# motor-drive.net
KiCad netlist of a schematic drawn in Altium Designer
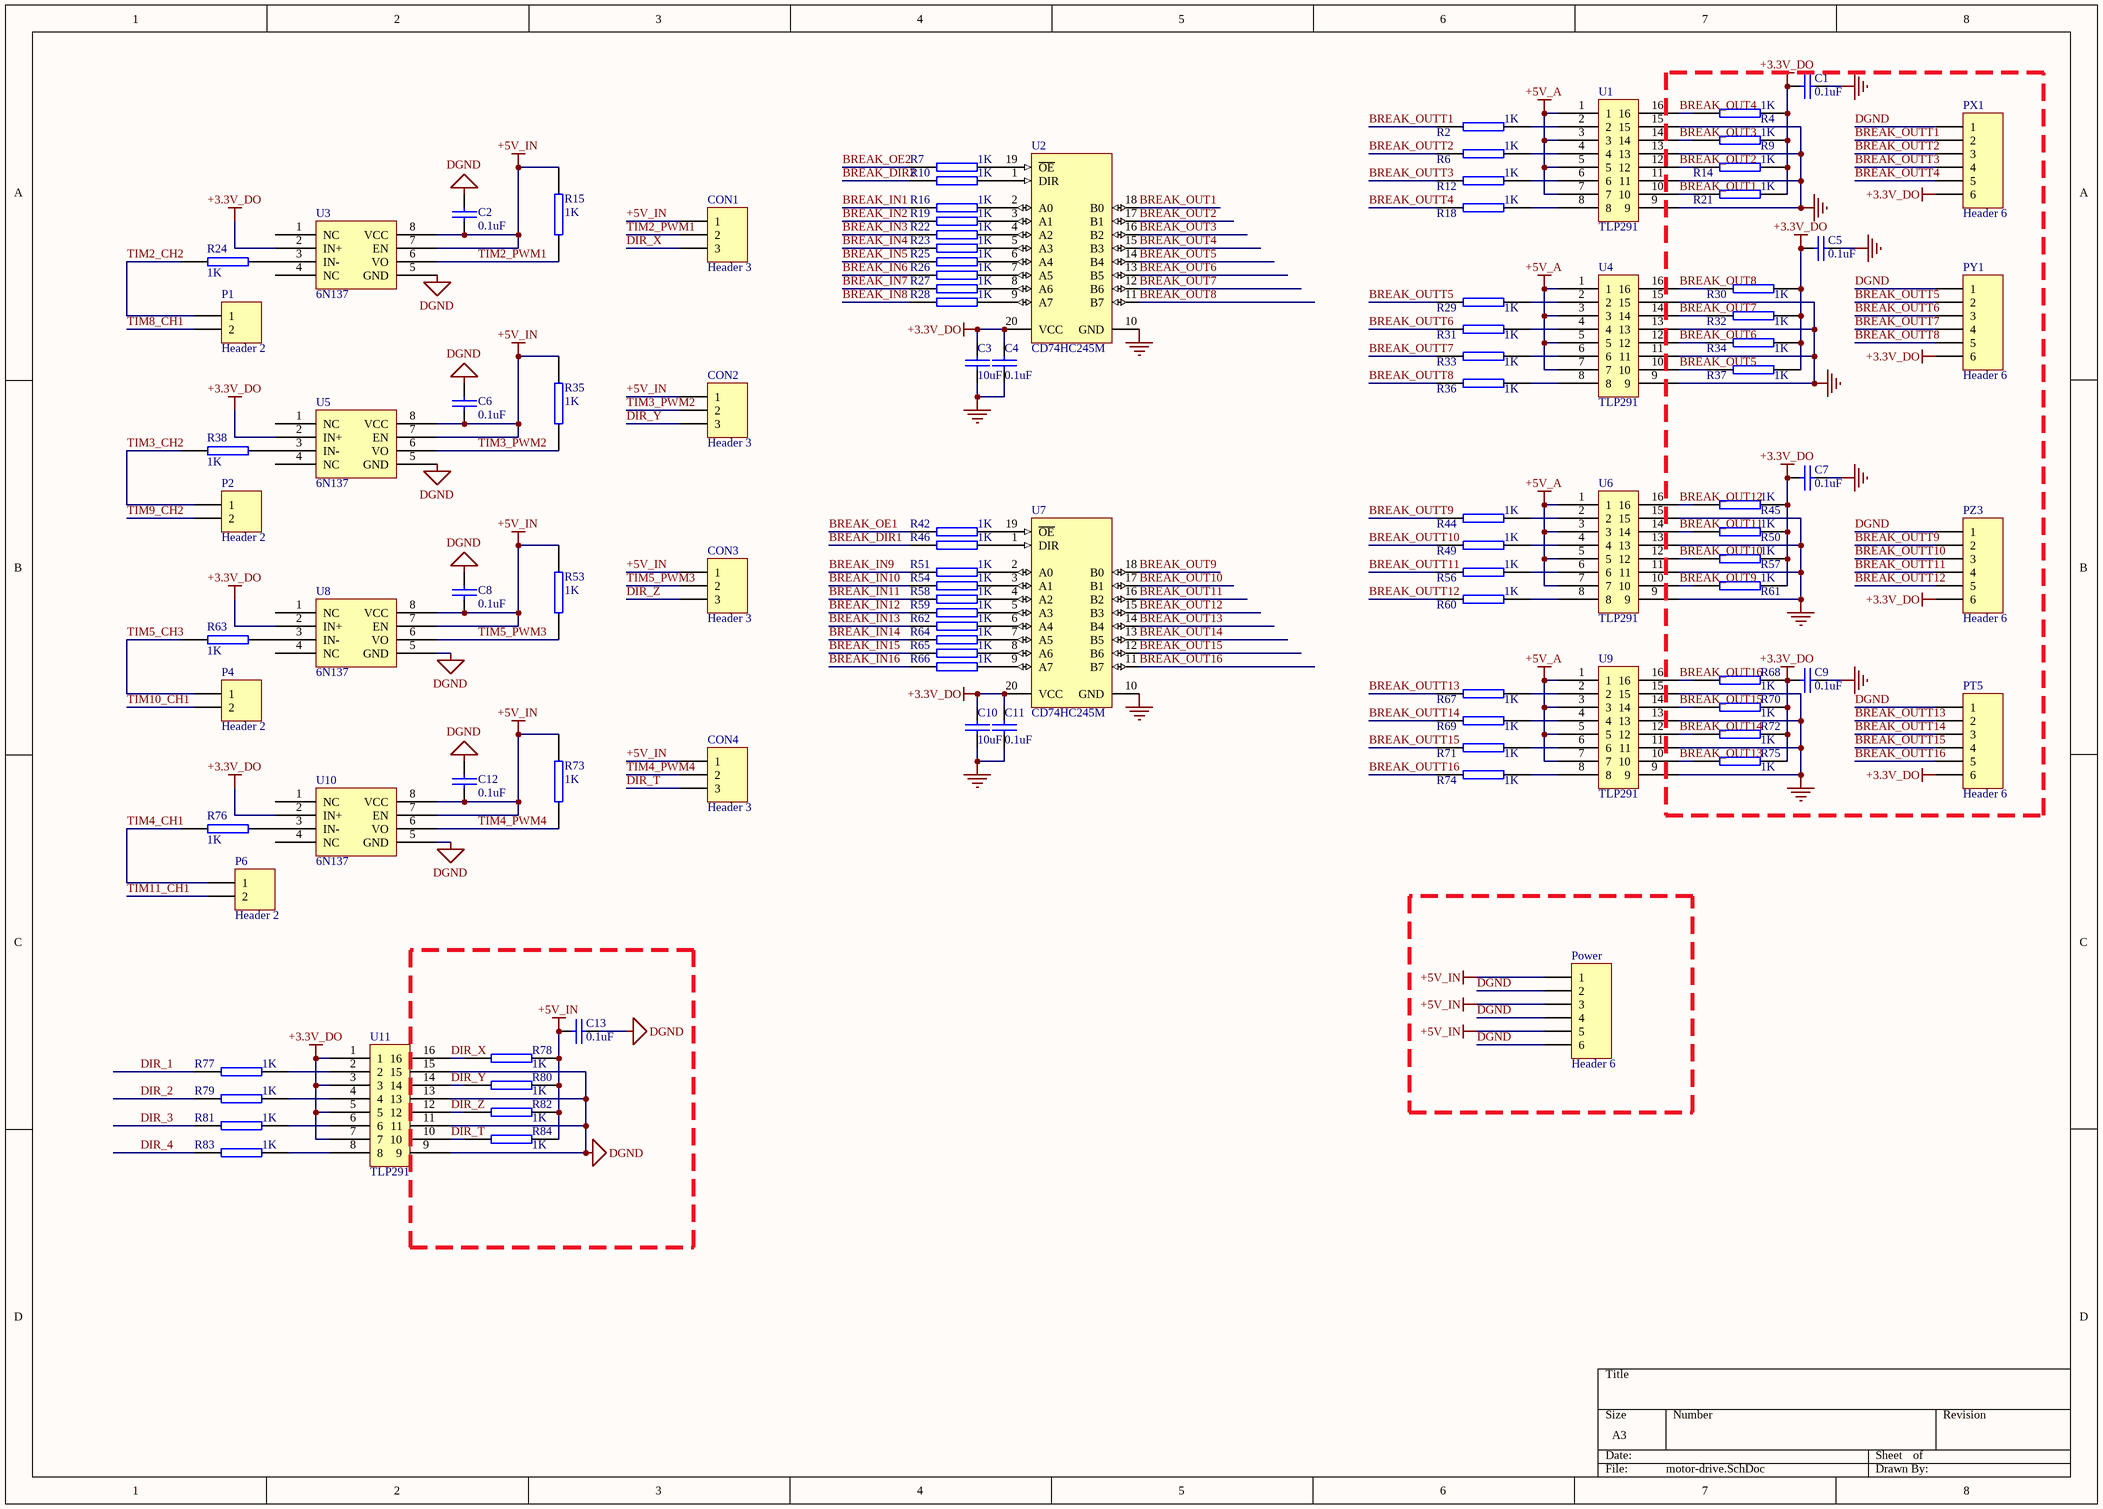
[diagram p0: motor-drive.SchDoc]

(export (version "E")
  (design (tool "Eeschema 10.0.6"))
  (components
    (comp (ref "C1")
      (value "0.1uF")
      (footprint "0805")
      (description "Capacitor")
      (libsource (lib "*") (part "CAP"))
    )
    (comp (ref "C2")
      (value "0.1uF")
      (footprint "0805")
      (description "Capacitor")
      (libsource (lib "*") (part "CAP"))
    )
    (comp (ref "C3")
      (value "10uF")
      (footprint "0805")
      (description "Capacitor")
      (libsource (lib "*") (part "CAP"))
    )
    (comp (ref "C4")
      (value "0.1uF")
      (footprint "0805")
      (description "Capacitor")
      (libsource (lib "*") (part "CAP"))
    )
    (comp (ref "C5")
      (value "0.1uF")
      (footprint "0805")
      (description "Capacitor")
      (libsource (lib "*") (part "CAP"))
    )
    (comp (ref "C6")
      (value "0.1uF")
      (footprint "0805")
      (description "Capacitor")
      (libsource (lib "*") (part "CAP"))
    )
    (comp (ref "C7")
      (value "0.1uF")
      (footprint "0805")
      (description "Capacitor")
      (libsource (lib "*") (part "CAP"))
    )
    (comp (ref "C8")
      (value "0.1uF")
      (footprint "0805")
      (description "Capacitor")
      (libsource (lib "*") (part "CAP"))
    )
    (comp (ref "C9")
      (value "0.1uF")
      (footprint "0805")
      (description "Capacitor")
      (libsource (lib "*") (part "CAP"))
    )
    (comp (ref "C10")
      (value "10uF")
      (footprint "0805")
      (description "Capacitor")
      (libsource (lib "*") (part "CAP"))
    )
    (comp (ref "C11")
      (value "0.1uF")
      (footprint "0805")
      (description "Capacitor")
      (libsource (lib "*") (part "CAP"))
    )
    (comp (ref "C12")
      (value "0.1uF")
      (footprint "0805")
      (description "Capacitor")
      (libsource (lib "*") (part "CAP"))
    )
    (comp (ref "C13")
      (value "0.1uF")
      (footprint "0805")
      (description "Capacitor")
      (libsource (lib "*") (part "CAP"))
    )
    (comp (ref "CON1")
      (value "Header 3")
      (footprint "CON3")
      (description "Header, 3-Pin")
      (fields (field (name "PUBLISHER") "Altium Limited"))
      (libsource (lib "Miscellaneous Connectors") (part "Header 3"))
    )
    (comp (ref "CON2")
      (value "Header 3")
      (footprint "CON3")
      (description "Header, 3-Pin")
      (fields (field (name "PUBLISHER") "Altium Limited"))
      (libsource (lib "Miscellaneous Connectors") (part "Header 3"))
    )
    (comp (ref "CON3")
      (value "Header 3")
      (footprint "CON3")
      (description "Header, 3-Pin")
      (fields (field (name "PUBLISHER") "Altium Limited"))
      (libsource (lib "Miscellaneous Connectors") (part "Header 3"))
    )
    (comp (ref "CON4")
      (value "Header 3")
      (footprint "CON3")
      (description "Header, 3-Pin")
      (fields (field (name "PUBLISHER") "Altium Limited"))
      (libsource (lib "Miscellaneous Connectors") (part "Header 3"))
    )
    (comp (ref "P1")
      (value "Header 2")
      (footprint "HDR1X2")
      (description "Header, 2-Pin")
      (fields (field (name "PUBLISHER") "Altium Limited"))
      (libsource (lib "Miscellaneous Connectors") (part "Header 2"))
    )
    (comp (ref "P2")
      (value "Header 2")
      (footprint "HDR1X2")
      (description "Header, 2-Pin")
      (fields (field (name "PUBLISHER") "Altium Limited"))
      (libsource (lib "Miscellaneous Connectors") (part "Header 2"))
    )
    (comp (ref "P4")
      (value "Header 2")
      (footprint "HDR1X2")
      (description "Header, 2-Pin")
      (fields (field (name "PUBLISHER") "Altium Limited"))
      (libsource (lib "Miscellaneous Connectors") (part "Header 2"))
    )
    (comp (ref "P6")
      (value "Header 2")
      (footprint "HDR1X2")
      (description "Header, 2-Pin")
      (fields (field (name "PUBLISHER") "Altium Limited"))
      (libsource (lib "Miscellaneous Connectors") (part "Header 2"))
    )
    (comp (ref "Power")
      (value "Header 6")
      (footprint "HDR1X6")
      (description "Header, 6-Pin")
      (fields (field (name "PUBLISHER") "Altium Limited"))
      (libsource (lib "Miscellaneous Connectors") (part "Header 6"))
    )
    (comp (ref "PT5")
      (value "Header 6")
      (footprint "HDR1X6")
      (description "Header, 6-Pin")
      (fields (field (name "PUBLISHER") "Altium Limited"))
      (libsource (lib "Miscellaneous Connectors") (part "Header 6"))
    )
    (comp (ref "PX1")
      (value "Header 6")
      (footprint "HDR1X6")
      (description "Header, 6-Pin")
      (fields (field (name "PUBLISHER") "Altium Limited"))
      (libsource (lib "Miscellaneous Connectors") (part "Header 6"))
    )
    (comp (ref "PY1")
      (value "Header 6")
      (footprint "HDR1X6")
      (description "Header, 6-Pin")
      (fields (field (name "PUBLISHER") "Altium Limited"))
      (libsource (lib "Miscellaneous Connectors") (part "Header 6"))
    )
    (comp (ref "PZ3")
      (value "Header 6")
      (footprint "HDR1X6")
      (description "Header, 6-Pin")
      (fields (field (name "PUBLISHER") "Altium Limited"))
      (libsource (lib "Miscellaneous Connectors") (part "Header 6"))
    )
    (comp (ref "R2") (value "1K") (footprint "0805") (libsource (lib "*") (part "RES2")))
    (comp (ref "R4") (value "1K") (footprint "0805") (libsource (lib "*") (part "RES2")))
    (comp (ref "R6") (value "1K") (footprint "0805") (libsource (lib "*") (part "RES2")))
    (comp (ref "R7") (value "1K") (footprint "0805") (libsource (lib "*") (part "RES2")))
    (comp (ref "R9") (value "1K") (footprint "0805") (libsource (lib "*") (part "RES2")))
    (comp (ref "R10") (value "1K") (footprint "0805") (libsource (lib "*") (part "RES2")))
    (comp (ref "R12") (value "1K") (footprint "0805") (libsource (lib "*") (part "RES2")))
    (comp (ref "R14") (value "1K") (footprint "0805") (libsource (lib "*") (part "RES2")))
    (comp (ref "R15") (value "1K") (footprint "0805") (libsource (lib "*") (part "RES2")))
    (comp (ref "R16") (value "1K") (footprint "0805") (libsource (lib "*") (part "RES2")))
    (comp (ref "R18") (value "1K") (footprint "0805") (libsource (lib "*") (part "RES2")))
    (comp (ref "R19") (value "1K") (footprint "0805") (libsource (lib "*") (part "RES2")))
    (comp (ref "R21") (value "1K") (footprint "0805") (libsource (lib "*") (part "RES2")))
    (comp (ref "R22") (value "1K") (footprint "0805") (libsource (lib "*") (part "RES2")))
    (comp (ref "R23") (value "1K") (footprint "0805") (libsource (lib "*") (part "RES2")))
    (comp (ref "R24") (value "1K") (footprint "0805") (libsource (lib "*") (part "RES2")))
    (comp (ref "R25") (value "1K") (footprint "0805") (libsource (lib "*") (part "RES2")))
    (comp (ref "R26") (value "1K") (footprint "0805") (libsource (lib "*") (part "RES2")))
    (comp (ref "R27") (value "1K") (footprint "0805") (libsource (lib "*") (part "RES2")))
    (comp (ref "R28") (value "1K") (footprint "0805") (libsource (lib "*") (part "RES2")))
    (comp (ref "R29") (value "1K") (footprint "0805") (libsource (lib "*") (part "RES2")))
    (comp (ref "R30") (value "1K") (footprint "0805") (libsource (lib "*") (part "RES2")))
    (comp (ref "R31") (value "1K") (footprint "0805") (libsource (lib "*") (part "RES2")))
    (comp (ref "R32") (value "1K") (footprint "0805") (libsource (lib "*") (part "RES2")))
    (comp (ref "R33") (value "1K") (footprint "0805") (libsource (lib "*") (part "RES2")))
    (comp (ref "R34") (value "1K") (footprint "0805") (libsource (lib "*") (part "RES2")))
    (comp (ref "R35") (value "1K") (footprint "0805") (libsource (lib "*") (part "RES2")))
    (comp (ref "R36") (value "1K") (footprint "0805") (libsource (lib "*") (part "RES2")))
    (comp (ref "R37") (value "1K") (footprint "0805") (libsource (lib "*") (part "RES2")))
    (comp (ref "R38") (value "1K") (footprint "0805") (libsource (lib "*") (part "RES2")))
    (comp (ref "R42") (value "1K") (footprint "0805") (libsource (lib "*") (part "RES2")))
    (comp (ref "R44") (value "1K") (footprint "0805") (libsource (lib "*") (part "RES2")))
    (comp (ref "R45") (value "1K") (footprint "0805") (libsource (lib "*") (part "RES2")))
    (comp (ref "R46") (value "1K") (footprint "0805") (libsource (lib "*") (part "RES2")))
    (comp (ref "R49") (value "1K") (footprint "0805") (libsource (lib "*") (part "RES2")))
    (comp (ref "R50") (value "1K") (footprint "0805") (libsource (lib "*") (part "RES2")))
    (comp (ref "R51") (value "1K") (footprint "0805") (libsource (lib "*") (part "RES2")))
    (comp (ref "R53") (value "1K") (footprint "0805") (libsource (lib "*") (part "RES2")))
    (comp (ref "R54") (value "1K") (footprint "0805") (libsource (lib "*") (part "RES2")))
    (comp (ref "R56") (value "1K") (footprint "0805") (libsource (lib "*") (part "RES2")))
    (comp (ref "R57") (value "1K") (footprint "0805") (libsource (lib "*") (part "RES2")))
    (comp (ref "R58") (value "1K") (footprint "0805") (libsource (lib "*") (part "RES2")))
    (comp (ref "R59") (value "1K") (footprint "0805") (libsource (lib "*") (part "RES2")))
    (comp (ref "R60") (value "1K") (footprint "0805") (libsource (lib "*") (part "RES2")))
    (comp (ref "R61") (value "1K") (footprint "0805") (libsource (lib "*") (part "RES2")))
    (comp (ref "R62") (value "1K") (footprint "0805") (libsource (lib "*") (part "RES2")))
    (comp (ref "R63") (value "1K") (footprint "0805") (libsource (lib "*") (part "RES2")))
    (comp (ref "R64") (value "1K") (footprint "0805") (libsource (lib "*") (part "RES2")))
    (comp (ref "R65") (value "1K") (footprint "0805") (libsource (lib "*") (part "RES2")))
    (comp (ref "R66") (value "1K") (footprint "0805") (libsource (lib "*") (part "RES2")))
    (comp (ref "R67") (value "1K") (footprint "0805") (libsource (lib "*") (part "RES2")))
    (comp (ref "R68") (value "1K") (footprint "0805") (libsource (lib "*") (part "RES2")))
    (comp (ref "R69") (value "1K") (footprint "0805") (libsource (lib "*") (part "RES2")))
    (comp (ref "R70") (value "1K") (footprint "0805") (libsource (lib "*") (part "RES2")))
    (comp (ref "R71") (value "1K") (footprint "0805") (libsource (lib "*") (part "RES2")))
    (comp (ref "R72") (value "1K") (footprint "0805") (libsource (lib "*") (part "RES2")))
    (comp (ref "R73") (value "1K") (footprint "0805") (libsource (lib "*") (part "RES2")))
    (comp (ref "R74") (value "1K") (footprint "0805") (libsource (lib "*") (part "RES2")))
    (comp (ref "R75") (value "1K") (footprint "0805") (libsource (lib "*") (part "RES2")))
    (comp (ref "R76") (value "1K") (footprint "0805") (libsource (lib "*") (part "RES2")))
    (comp (ref "R77") (value "1K") (footprint "0805") (libsource (lib "*") (part "RES2")))
    (comp (ref "R78") (value "1K") (footprint "0805") (libsource (lib "*") (part "RES2")))
    (comp (ref "R79") (value "1K") (footprint "0805") (libsource (lib "*") (part "RES2")))
    (comp (ref "R80") (value "1K") (footprint "0805") (libsource (lib "*") (part "RES2")))
    (comp (ref "R81") (value "1K") (footprint "0805") (libsource (lib "*") (part "RES2")))
    (comp (ref "R82") (value "1K") (footprint "0805") (libsource (lib "*") (part "RES2")))
    (comp (ref "R83") (value "1K") (footprint "0805") (libsource (lib "*") (part "RES2")))
    (comp (ref "R84") (value "1K") (footprint "0805") (libsource (lib "*") (part "RES2")))
    (comp (ref "U1")
      (value "TLP291")
      (footprint "SOIC-TLP291-4-16N")
      (description "光耦隔离")
      (libsource (lib "tlp291-4") (part "TLP291-4"))
    )
    (comp (ref "U2")
      (value "CD74HC245M")
      (footprint "DW0020A_N")
      (description "High Speed CMOS Logic Non-Inverting Octal-Bus Transceivers with 3-State Outputs, DW0020A, TUBE")
      (fields
        (field (name "GENERIC PART NUMBER") "CD74HC245")
        (field (name "MANUFACTURER") "Texas Instruments")
      )
      (libsource (lib "TI_Logic_Buffer,Driver,Transceiver") (part "CD74HC245M"))
    )
    (comp (ref "U3") (value "6N137") (footprint "SO-8") (libsource (lib "*") (part "HCPL2400")))
    (comp (ref "U4")
      (value "TLP291")
      (footprint "SOIC-TLP291-4-16N")
      (description "光耦隔离")
      (libsource (lib "tlp291-4") (part "TLP291-4"))
    )
    (comp (ref "U5") (value "6N137") (footprint "SO-8") (libsource (lib "*") (part "HCPL2400")))
    (comp (ref "U6")
      (value "TLP291")
      (footprint "SOIC-TLP291-4-16N")
      (description "光耦隔离")
      (libsource (lib "tlp291-4") (part "TLP291-4"))
    )
    (comp (ref "U7")
      (value "CD74HC245M")
      (footprint "DW0020A_N")
      (description "High Speed CMOS Logic Non-Inverting Octal-Bus Transceivers with 3-State Outputs, DW0020A, TUBE")
      (fields
        (field (name "GENERIC PART NUMBER") "CD74HC245")
        (field (name "MANUFACTURER") "Texas Instruments")
      )
      (libsource (lib "TI_Logic_Buffer,Driver,Transceiver") (part "CD74HC245M"))
    )
    (comp (ref "U8") (value "6N137") (footprint "SO-8") (libsource (lib "*") (part "HCPL2400")))
    (comp (ref "U9")
      (value "TLP291")
      (footprint "SOIC-TLP291-4-16N")
      (description "光耦隔离")
      (libsource (lib "tlp291-4") (part "TLP291-4"))
    )
    (comp (ref "U10") (value "6N137") (footprint "SO-8") (libsource (lib "*") (part "HCPL2400")))
    (comp (ref "U11")
      (value "TLP291")
      (footprint "SOIC-TLP291-4-16N")
      (description "光耦隔离")
      (libsource (lib "tlp291-4") (part "TLP291-4"))
    )
  )
  (nets
    (net (code "1") (name "+3.3V_DO") (class "Default")
      (node (ref "C1") (pin "1") (pinfunction "1_1") (pintype "passive"))
      (node (ref "C10") (pin "1") (pinfunction "1_1") (pintype "passive"))
      (node (ref "C11") (pin "2") (pinfunction "2_2") (pintype "passive"))
      (node (ref "C3") (pin "1") (pinfunction "1_1") (pintype "passive"))
      (node (ref "C4") (pin "2") (pinfunction "2_2") (pintype "passive"))
      (node (ref "C5") (pin "1") (pinfunction "1_1") (pintype "passive"))
      (node (ref "C7") (pin "1") (pinfunction "1_1") (pintype "passive"))
      (node (ref "C9") (pin "1") (pinfunction "1_1") (pintype "passive"))
      (node (ref "PT5") (pin "6") (pinfunction "6_6") (pintype "passive"))
      (node (ref "PX1") (pin "6") (pinfunction "6_6") (pintype "passive"))
      (node (ref "PY1") (pin "6") (pinfunction "6_6") (pintype "passive"))
      (node (ref "PZ3") (pin "6") (pinfunction "6_6") (pintype "passive"))
      (node (ref "R14") (pin "1") (pinfunction "1_1") (pintype "passive"))
      (node (ref "R21") (pin "1") (pinfunction "1_1") (pintype "passive"))
      (node (ref "R30") (pin "1") (pinfunction "1_1") (pintype "passive"))
      (node (ref "R32") (pin "1") (pinfunction "1_1") (pintype "passive"))
      (node (ref "R34") (pin "1") (pinfunction "1_1") (pintype "passive"))
      (node (ref "R37") (pin "1") (pinfunction "1_1") (pintype "passive"))
      (node (ref "R4") (pin "1") (pinfunction "1_1") (pintype "passive"))
      (node (ref "R45") (pin "1") (pinfunction "1_1") (pintype "passive"))
      (node (ref "R50") (pin "1") (pinfunction "1_1") (pintype "passive"))
      (node (ref "R57") (pin "1") (pinfunction "1_1") (pintype "passive"))
      (node (ref "R61") (pin "1") (pinfunction "1_1") (pintype "passive"))
      (node (ref "R68") (pin "1") (pinfunction "1_1") (pintype "passive"))
      (node (ref "R70") (pin "1") (pinfunction "1_1") (pintype "passive"))
      (node (ref "R72") (pin "1") (pinfunction "1_1") (pintype "passive"))
      (node (ref "R75") (pin "1") (pinfunction "1_1") (pintype "passive"))
      (node (ref "R9") (pin "1") (pinfunction "1_1") (pintype "passive"))
      (node (ref "U10") (pin "2") (pinfunction "IN+_2") (pintype "passive"))
      (node (ref "U11") (pin "1") (pinfunction "1_1") (pintype "passive"))
      (node (ref "U11") (pin "3") (pinfunction "3_3") (pintype "passive"))
      (node (ref "U11") (pin "5") (pinfunction "5_5") (pintype "passive"))
      (node (ref "U11") (pin "7") (pinfunction "7_7") (pintype "passive"))
      (node (ref "U2") (pin "20") (pinfunction "VCC_20") (pintype "power_in"))
      (node (ref "U3") (pin "2") (pinfunction "IN+_2") (pintype "passive"))
      (node (ref "U5") (pin "2") (pinfunction "IN+_2") (pintype "passive"))
      (node (ref "U7") (pin "20") (pinfunction "VCC_20") (pintype "power_in"))
      (node (ref "U8") (pin "2") (pinfunction "IN+_2") (pintype "passive"))
    )
    (net (code "2") (name "+5V_A") (class "Default")
      (node (ref "U1") (pin "1") (pinfunction "1_1") (pintype "passive"))
      (node (ref "U1") (pin "3") (pinfunction "3_3") (pintype "passive"))
      (node (ref "U1") (pin "5") (pinfunction "5_5") (pintype "passive"))
      (node (ref "U1") (pin "7") (pinfunction "7_7") (pintype "passive"))
      (node (ref "U4") (pin "1") (pinfunction "1_1") (pintype "passive"))
      (node (ref "U4") (pin "3") (pinfunction "3_3") (pintype "passive"))
      (node (ref "U4") (pin "5") (pinfunction "5_5") (pintype "passive"))
      (node (ref "U4") (pin "7") (pinfunction "7_7") (pintype "passive"))
      (node (ref "U6") (pin "1") (pinfunction "1_1") (pintype "passive"))
      (node (ref "U6") (pin "3") (pinfunction "3_3") (pintype "passive"))
      (node (ref "U6") (pin "5") (pinfunction "5_5") (pintype "passive"))
      (node (ref "U6") (pin "7") (pinfunction "7_7") (pintype "passive"))
      (node (ref "U9") (pin "1") (pinfunction "1_1") (pintype "passive"))
      (node (ref "U9") (pin "3") (pinfunction "3_3") (pintype "passive"))
      (node (ref "U9") (pin "5") (pinfunction "5_5") (pintype "passive"))
      (node (ref "U9") (pin "7") (pinfunction "7_7") (pintype "passive"))
    )
    (net (code "3") (name "+5V_IN") (class "Default")
      (node (ref "C12") (pin "2") (pinfunction "2_2") (pintype "passive"))
      (node (ref "C13") (pin "1") (pinfunction "1_1") (pintype "passive"))
      (node (ref "C2") (pin "2") (pinfunction "2_2") (pintype "passive"))
      (node (ref "C6") (pin "2") (pinfunction "2_2") (pintype "passive"))
      (node (ref "C8") (pin "2") (pinfunction "2_2") (pintype "passive"))
      (node (ref "CON1") (pin "1") (pinfunction "1_1") (pintype "passive"))
      (node (ref "CON2") (pin "1") (pinfunction "1_1") (pintype "passive"))
      (node (ref "CON3") (pin "1") (pinfunction "1_1") (pintype "passive"))
      (node (ref "CON4") (pin "1") (pinfunction "1_1") (pintype "passive"))
      (node (ref "Power") (pin "1") (pinfunction "1_1") (pintype "passive"))
      (node (ref "Power") (pin "3") (pinfunction "3_3") (pintype "passive"))
      (node (ref "Power") (pin "5") (pinfunction "5_5") (pintype "passive"))
      (node (ref "R15") (pin "2") (pinfunction "2_2") (pintype "passive"))
      (node (ref "R35") (pin "2") (pinfunction "2_2") (pintype "passive"))
      (node (ref "R53") (pin "2") (pinfunction "2_2") (pintype "passive"))
      (node (ref "R73") (pin "2") (pinfunction "2_2") (pintype "passive"))
      (node (ref "R78") (pin "2") (pinfunction "2_2") (pintype "passive"))
      (node (ref "R80") (pin "1") (pinfunction "1_1") (pintype "passive"))
      (node (ref "R82") (pin "1") (pinfunction "1_1") (pintype "passive"))
      (node (ref "R84") (pin "1") (pinfunction "1_1") (pintype "passive"))
      (node (ref "U10") (pin "7") (pinfunction "EN_7") (pintype "passive"))
      (node (ref "U10") (pin "8") (pinfunction "VCC_8") (pintype "passive"))
      (node (ref "U3") (pin "7") (pinfunction "EN_7") (pintype "passive"))
      (node (ref "U3") (pin "8") (pinfunction "VCC_8") (pintype "passive"))
      (node (ref "U5") (pin "7") (pinfunction "EN_7") (pintype "passive"))
      (node (ref "U5") (pin "8") (pinfunction "VCC_8") (pintype "passive"))
      (node (ref "U8") (pin "7") (pinfunction "EN_7") (pintype "passive"))
      (node (ref "U8") (pin "8") (pinfunction "VCC_8") (pintype "passive"))
    )
    (net (code "4") (name "/BREAK_DIR1") (class "Default")
      (node (ref "R46") (pin "1") (pinfunction "1_1") (pintype "passive"))
    )
    (net (code "5") (name "/BREAK_DIR2") (class "Default")
      (node (ref "R10") (pin "1") (pinfunction "1_1") (pintype "passive"))
    )
    (net (code "6") (name "/BREAK_IN1") (class "Default")
      (node (ref "R16") (pin "1") (pinfunction "1_1") (pintype "passive"))
    )
    (net (code "7") (name "/BREAK_IN2") (class "Default")
      (node (ref "R19") (pin "1") (pinfunction "1_1") (pintype "passive"))
    )
    (net (code "8") (name "/BREAK_IN3") (class "Default")
      (node (ref "R22") (pin "1") (pinfunction "1_1") (pintype "passive"))
    )
    (net (code "9") (name "/BREAK_IN4") (class "Default")
      (node (ref "R23") (pin "1") (pinfunction "1_1") (pintype "passive"))
    )
    (net (code "10") (name "/BREAK_IN5") (class "Default")
      (node (ref "R25") (pin "1") (pinfunction "1_1") (pintype "passive"))
    )
    (net (code "11") (name "/BREAK_IN6") (class "Default")
      (node (ref "R26") (pin "1") (pinfunction "1_1") (pintype "passive"))
    )
    (net (code "12") (name "/BREAK_IN7") (class "Default")
      (node (ref "R27") (pin "1") (pinfunction "1_1") (pintype "passive"))
    )
    (net (code "13") (name "/BREAK_IN8") (class "Default")
      (node (ref "R28") (pin "1") (pinfunction "1_1") (pintype "passive"))
    )
    (net (code "14") (name "/BREAK_IN9") (class "Default")
      (node (ref "R51") (pin "1") (pinfunction "1_1") (pintype "passive"))
    )
    (net (code "15") (name "/BREAK_IN10") (class "Default")
      (node (ref "R54") (pin "1") (pinfunction "1_1") (pintype "passive"))
    )
    (net (code "16") (name "/BREAK_IN11") (class "Default")
      (node (ref "R58") (pin "1") (pinfunction "1_1") (pintype "passive"))
    )
    (net (code "17") (name "/BREAK_IN12") (class "Default")
      (node (ref "R59") (pin "1") (pinfunction "1_1") (pintype "passive"))
    )
    (net (code "18") (name "/BREAK_IN13") (class "Default")
      (node (ref "R62") (pin "1") (pinfunction "1_1") (pintype "passive"))
    )
    (net (code "19") (name "/BREAK_IN14") (class "Default")
      (node (ref "R64") (pin "1") (pinfunction "1_1") (pintype "passive"))
    )
    (net (code "20") (name "/BREAK_IN15") (class "Default")
      (node (ref "R65") (pin "1") (pinfunction "1_1") (pintype "passive"))
    )
    (net (code "21") (name "/BREAK_IN16") (class "Default")
      (node (ref "R66") (pin "1") (pinfunction "1_1") (pintype "passive"))
    )
    (net (code "22") (name "/BREAK_OE1") (class "Default")
      (node (ref "R42") (pin "1") (pinfunction "1_1") (pintype "passive"))
    )
    (net (code "23") (name "/BREAK_OE2") (class "Default")
      (node (ref "R7") (pin "1") (pinfunction "1_1") (pintype "passive"))
    )
    (net (code "24") (name "/BREAK_OUT1") (class "Default")
      (node (ref "R21") (pin "2") (pinfunction "2_2") (pintype "passive"))
      (node (ref "U1") (pin "10") (pinfunction "10_10") (pintype "passive"))
      (node (ref "U2") (pin "18") (pinfunction "B0_18") (pintype "bidirectional"))
    )
    (net (code "25") (name "/BREAK_OUT2") (class "Default")
      (node (ref "R14") (pin "2") (pinfunction "2_2") (pintype "passive"))
      (node (ref "U1") (pin "12") (pinfunction "12_12") (pintype "passive"))
      (node (ref "U2") (pin "17") (pinfunction "B1_17") (pintype "bidirectional"))
    )
    (net (code "26") (name "/BREAK_OUT3") (class "Default")
      (node (ref "R9") (pin "2") (pinfunction "2_2") (pintype "passive"))
      (node (ref "U1") (pin "14") (pinfunction "14_14") (pintype "passive"))
      (node (ref "U2") (pin "16") (pinfunction "B2_16") (pintype "bidirectional"))
    )
    (net (code "27") (name "/BREAK_OUT4") (class "Default")
      (node (ref "R4") (pin "2") (pinfunction "2_2") (pintype "passive"))
      (node (ref "U1") (pin "16") (pinfunction "16_16") (pintype "passive"))
      (node (ref "U2") (pin "15") (pinfunction "B3_15") (pintype "bidirectional"))
    )
    (net (code "28") (name "/BREAK_OUT5") (class "Default")
      (node (ref "R37") (pin "2") (pinfunction "2_2") (pintype "passive"))
      (node (ref "U2") (pin "14") (pinfunction "B4_14") (pintype "bidirectional"))
      (node (ref "U4") (pin "10") (pinfunction "10_10") (pintype "passive"))
    )
    (net (code "29") (name "/BREAK_OUT6") (class "Default")
      (node (ref "R34") (pin "2") (pinfunction "2_2") (pintype "passive"))
      (node (ref "U2") (pin "13") (pinfunction "B5_13") (pintype "bidirectional"))
      (node (ref "U4") (pin "12") (pinfunction "12_12") (pintype "passive"))
    )
    (net (code "30") (name "/BREAK_OUT7") (class "Default")
      (node (ref "R32") (pin "2") (pinfunction "2_2") (pintype "passive"))
      (node (ref "U2") (pin "12") (pinfunction "B6_12") (pintype "bidirectional"))
      (node (ref "U4") (pin "14") (pinfunction "14_14") (pintype "passive"))
    )
    (net (code "31") (name "/BREAK_OUT8") (class "Default")
      (node (ref "R30") (pin "2") (pinfunction "2_2") (pintype "passive"))
      (node (ref "U2") (pin "11") (pinfunction "B7_11") (pintype "bidirectional"))
      (node (ref "U4") (pin "16") (pinfunction "16_16") (pintype "passive"))
    )
    (net (code "32") (name "/BREAK_OUT9") (class "Default")
      (node (ref "R61") (pin "2") (pinfunction "2_2") (pintype "passive"))
      (node (ref "U6") (pin "10") (pinfunction "10_10") (pintype "passive"))
      (node (ref "U7") (pin "18") (pinfunction "B0_18") (pintype "bidirectional"))
    )
    (net (code "33") (name "/BREAK_OUT10") (class "Default")
      (node (ref "R57") (pin "2") (pinfunction "2_2") (pintype "passive"))
      (node (ref "U6") (pin "12") (pinfunction "12_12") (pintype "passive"))
      (node (ref "U7") (pin "17") (pinfunction "B1_17") (pintype "bidirectional"))
    )
    (net (code "34") (name "/BREAK_OUT11") (class "Default")
      (node (ref "R50") (pin "2") (pinfunction "2_2") (pintype "passive"))
      (node (ref "U6") (pin "14") (pinfunction "14_14") (pintype "passive"))
      (node (ref "U7") (pin "16") (pinfunction "B2_16") (pintype "bidirectional"))
    )
    (net (code "35") (name "/BREAK_OUT12") (class "Default")
      (node (ref "R45") (pin "2") (pinfunction "2_2") (pintype "passive"))
      (node (ref "U6") (pin "16") (pinfunction "16_16") (pintype "passive"))
      (node (ref "U7") (pin "15") (pinfunction "B3_15") (pintype "bidirectional"))
    )
    (net (code "36") (name "/BREAK_OUT13") (class "Default")
      (node (ref "R75") (pin "2") (pinfunction "2_2") (pintype "passive"))
      (node (ref "U7") (pin "14") (pinfunction "B4_14") (pintype "bidirectional"))
      (node (ref "U9") (pin "10") (pinfunction "10_10") (pintype "passive"))
    )
    (net (code "37") (name "/BREAK_OUT14") (class "Default")
      (node (ref "R72") (pin "2") (pinfunction "2_2") (pintype "passive"))
      (node (ref "U7") (pin "13") (pinfunction "B5_13") (pintype "bidirectional"))
      (node (ref "U9") (pin "12") (pinfunction "12_12") (pintype "passive"))
    )
    (net (code "38") (name "/BREAK_OUT15") (class "Default")
      (node (ref "R70") (pin "2") (pinfunction "2_2") (pintype "passive"))
      (node (ref "U7") (pin "12") (pinfunction "B6_12") (pintype "bidirectional"))
      (node (ref "U9") (pin "14") (pinfunction "14_14") (pintype "passive"))
    )
    (net (code "39") (name "/BREAK_OUT16") (class "Default")
      (node (ref "R68") (pin "2") (pinfunction "2_2") (pintype "passive"))
      (node (ref "U7") (pin "11") (pinfunction "B7_11") (pintype "bidirectional"))
      (node (ref "U9") (pin "16") (pinfunction "16_16") (pintype "passive"))
    )
    (net (code "40") (name "/BREAK_OUTT1") (class "Default")
      (node (ref "PX1") (pin "2") (pinfunction "2_2") (pintype "passive"))
      (node (ref "R2") (pin "2") (pinfunction "2_2") (pintype "passive"))
    )
    (net (code "41") (name "/BREAK_OUTT2") (class "Default")
      (node (ref "PX1") (pin "3") (pinfunction "3_3") (pintype "passive"))
      (node (ref "R6") (pin "2") (pinfunction "2_2") (pintype "passive"))
    )
    (net (code "42") (name "/BREAK_OUTT3") (class "Default")
      (node (ref "PX1") (pin "4") (pinfunction "4_4") (pintype "passive"))
      (node (ref "R12") (pin "2") (pinfunction "2_2") (pintype "passive"))
    )
    (net (code "43") (name "/BREAK_OUTT4") (class "Default")
      (node (ref "PX1") (pin "5") (pinfunction "5_5") (pintype "passive"))
      (node (ref "R18") (pin "2") (pinfunction "2_2") (pintype "passive"))
    )
    (net (code "44") (name "/BREAK_OUTT5") (class "Default")
      (node (ref "PY1") (pin "2") (pinfunction "2_2") (pintype "passive"))
      (node (ref "R29") (pin "2") (pinfunction "2_2") (pintype "passive"))
    )
    (net (code "45") (name "/BREAK_OUTT6") (class "Default")
      (node (ref "PY1") (pin "3") (pinfunction "3_3") (pintype "passive"))
      (node (ref "R31") (pin "2") (pinfunction "2_2") (pintype "passive"))
    )
    (net (code "46") (name "/BREAK_OUTT7") (class "Default")
      (node (ref "PY1") (pin "4") (pinfunction "4_4") (pintype "passive"))
      (node (ref "R33") (pin "2") (pinfunction "2_2") (pintype "passive"))
    )
    (net (code "47") (name "/BREAK_OUTT8") (class "Default")
      (node (ref "PY1") (pin "5") (pinfunction "5_5") (pintype "passive"))
      (node (ref "R36") (pin "2") (pinfunction "2_2") (pintype "passive"))
    )
    (net (code "48") (name "/BREAK_OUTT9") (class "Default")
      (node (ref "PZ3") (pin "2") (pinfunction "2_2") (pintype "passive"))
      (node (ref "R44") (pin "2") (pinfunction "2_2") (pintype "passive"))
    )
    (net (code "49") (name "/BREAK_OUTT10") (class "Default")
      (node (ref "PZ3") (pin "3") (pinfunction "3_3") (pintype "passive"))
      (node (ref "R49") (pin "2") (pinfunction "2_2") (pintype "passive"))
    )
    (net (code "50") (name "/BREAK_OUTT11") (class "Default")
      (node (ref "PZ3") (pin "4") (pinfunction "4_4") (pintype "passive"))
      (node (ref "R56") (pin "2") (pinfunction "2_2") (pintype "passive"))
    )
    (net (code "51") (name "/BREAK_OUTT12") (class "Default")
      (node (ref "PZ3") (pin "5") (pinfunction "5_5") (pintype "passive"))
      (node (ref "R60") (pin "2") (pinfunction "2_2") (pintype "passive"))
    )
    (net (code "52") (name "/BREAK_OUTT13") (class "Default")
      (node (ref "PT5") (pin "2") (pinfunction "2_2") (pintype "passive"))
      (node (ref "R67") (pin "2") (pinfunction "2_2") (pintype "passive"))
    )
    (net (code "53") (name "/BREAK_OUTT14") (class "Default")
      (node (ref "PT5") (pin "3") (pinfunction "3_3") (pintype "passive"))
      (node (ref "R69") (pin "2") (pinfunction "2_2") (pintype "passive"))
    )
    (net (code "54") (name "/BREAK_OUTT15") (class "Default")
      (node (ref "PT5") (pin "4") (pinfunction "4_4") (pintype "passive"))
      (node (ref "R71") (pin "2") (pinfunction "2_2") (pintype "passive"))
    )
    (net (code "55") (name "/BREAK_OUTT16") (class "Default")
      (node (ref "PT5") (pin "5") (pinfunction "5_5") (pintype "passive"))
      (node (ref "R74") (pin "2") (pinfunction "2_2") (pintype "passive"))
    )
    (net (code "56") (name "/DIR_1") (class "Default")
      (node (ref "R77") (pin "2") (pinfunction "2_2") (pintype "passive"))
    )
    (net (code "57") (name "/DIR_2") (class "Default")
      (node (ref "R79") (pin "2") (pinfunction "2_2") (pintype "passive"))
    )
    (net (code "58") (name "/DIR_3") (class "Default")
      (node (ref "R81") (pin "2") (pinfunction "2_2") (pintype "passive"))
    )
    (net (code "59") (name "/DIR_4") (class "Default")
      (node (ref "R83") (pin "2") (pinfunction "2_2") (pintype "passive"))
    )
    (net (code "60") (name "/DIR_T") (class "Default")
      (node (ref "CON4") (pin "3") (pinfunction "3_3") (pintype "passive"))
      (node (ref "R84") (pin "2") (pinfunction "2_2") (pintype "passive"))
      (node (ref "U11") (pin "10") (pinfunction "10_10") (pintype "passive"))
    )
    (net (code "61") (name "/DIR_X") (class "Default")
      (node (ref "CON1") (pin "3") (pinfunction "3_3") (pintype "passive"))
      (node (ref "R78") (pin "1") (pinfunction "1_1") (pintype "passive"))
      (node (ref "U11") (pin "16") (pinfunction "16_16") (pintype "passive"))
    )
    (net (code "62") (name "/DIR_Y") (class "Default")
      (node (ref "CON2") (pin "3") (pinfunction "3_3") (pintype "passive"))
      (node (ref "R80") (pin "2") (pinfunction "2_2") (pintype "passive"))
      (node (ref "U11") (pin "14") (pinfunction "14_14") (pintype "passive"))
    )
    (net (code "63") (name "/DIR_Z") (class "Default")
      (node (ref "CON3") (pin "3") (pinfunction "3_3") (pintype "passive"))
      (node (ref "R82") (pin "2") (pinfunction "2_2") (pintype "passive"))
      (node (ref "U11") (pin "12") (pinfunction "12_12") (pintype "passive"))
    )
    (net (code "64") (name "/TIM2_CH2") (class "Default")
      (node (ref "P1") (pin "1") (pinfunction "1_1") (pintype "passive"))
      (node (ref "R24") (pin "1") (pinfunction "1_1") (pintype "passive"))
    )
    (net (code "65") (name "/TIM2_PWM1") (class "Default")
      (node (ref "CON1") (pin "2") (pinfunction "2_2") (pintype "passive"))
      (node (ref "R15") (pin "1") (pinfunction "1_1") (pintype "passive"))
      (node (ref "U3") (pin "6") (pinfunction "VO_6") (pintype "passive"))
    )
    (net (code "66") (name "/TIM3_CH2") (class "Default")
      (node (ref "P2") (pin "1") (pinfunction "1_1") (pintype "passive"))
      (node (ref "R38") (pin "1") (pinfunction "1_1") (pintype "passive"))
    )
    (net (code "67") (name "/TIM3_PWM2") (class "Default")
      (node (ref "CON2") (pin "2") (pinfunction "2_2") (pintype "passive"))
      (node (ref "R35") (pin "1") (pinfunction "1_1") (pintype "passive"))
      (node (ref "U5") (pin "6") (pinfunction "VO_6") (pintype "passive"))
    )
    (net (code "68") (name "/TIM4_CH1") (class "Default")
      (node (ref "P6") (pin "1") (pinfunction "1_1") (pintype "passive"))
      (node (ref "R76") (pin "1") (pinfunction "1_1") (pintype "passive"))
    )
    (net (code "69") (name "/TIM4_PWM4") (class "Default")
      (node (ref "CON4") (pin "2") (pinfunction "2_2") (pintype "passive"))
      (node (ref "R73") (pin "1") (pinfunction "1_1") (pintype "passive"))
      (node (ref "U10") (pin "6") (pinfunction "VO_6") (pintype "passive"))
    )
    (net (code "70") (name "/TIM5_CH3") (class "Default")
      (node (ref "P4") (pin "1") (pinfunction "1_1") (pintype "passive"))
      (node (ref "R63") (pin "1") (pinfunction "1_1") (pintype "passive"))
    )
    (net (code "71") (name "/TIM5_PWM3") (class "Default")
      (node (ref "CON3") (pin "2") (pinfunction "2_2") (pintype "passive"))
      (node (ref "R53") (pin "1") (pinfunction "1_1") (pintype "passive"))
      (node (ref "U8") (pin "6") (pinfunction "VO_6") (pintype "passive"))
    )
    (net (code "72") (name "/TIM8_CH1") (class "Default")
      (node (ref "P1") (pin "2") (pinfunction "2_2") (pintype "passive"))
    )
    (net (code "73") (name "/TIM9_CH2") (class "Default")
      (node (ref "P2") (pin "2") (pinfunction "2_2") (pintype "passive"))
    )
    (net (code "74") (name "/TIM10_CH1") (class "Default")
      (node (ref "P4") (pin "2") (pinfunction "2_2") (pintype "passive"))
    )
    (net (code "75") (name "/TIM11_CH1") (class "Default")
      (node (ref "P6") (pin "2") (pinfunction "2_2") (pintype "passive"))
    )
    (net (code "76") (name "DGND") (class "Default")
      (node (ref "C1") (pin "2") (pinfunction "2_2") (pintype "passive"))
      (node (ref "C10") (pin "2") (pinfunction "2_2") (pintype "passive"))
      (node (ref "C11") (pin "1") (pinfunction "1_1") (pintype "passive"))
      (node (ref "C12") (pin "1") (pinfunction "1_1") (pintype "passive"))
      (node (ref "C13") (pin "2") (pinfunction "2_2") (pintype "passive"))
      (node (ref "C2") (pin "1") (pinfunction "1_1") (pintype "passive"))
      (node (ref "C3") (pin "2") (pinfunction "2_2") (pintype "passive"))
      (node (ref "C4") (pin "1") (pinfunction "1_1") (pintype "passive"))
      (node (ref "C5") (pin "2") (pinfunction "2_2") (pintype "passive"))
      (node (ref "C6") (pin "1") (pinfunction "1_1") (pintype "passive"))
      (node (ref "C7") (pin "2") (pinfunction "2_2") (pintype "passive"))
      (node (ref "C8") (pin "1") (pinfunction "1_1") (pintype "passive"))
      (node (ref "C9") (pin "2") (pinfunction "2_2") (pintype "passive"))
      (node (ref "PT5") (pin "1") (pinfunction "1_1") (pintype "passive"))
      (node (ref "PX1") (pin "1") (pinfunction "1_1") (pintype "passive"))
      (node (ref "PY1") (pin "1") (pinfunction "1_1") (pintype "passive"))
      (node (ref "PZ3") (pin "1") (pinfunction "1_1") (pintype "passive"))
      (node (ref "Power") (pin "2") (pinfunction "2_2") (pintype "passive"))
      (node (ref "Power") (pin "4") (pinfunction "4_4") (pintype "passive"))
      (node (ref "Power") (pin "6") (pinfunction "6_6") (pintype "passive"))
      (node (ref "U1") (pin "11") (pinfunction "11_11") (pintype "passive"))
      (node (ref "U1") (pin "13") (pinfunction "13_13") (pintype "passive"))
      (node (ref "U1") (pin "15") (pinfunction "15_15") (pintype "passive"))
      (node (ref "U1") (pin "9") (pinfunction "9_9") (pintype "passive"))
      (node (ref "U10") (pin "5") (pinfunction "GND_5") (pintype "passive"))
      (node (ref "U11") (pin "11") (pinfunction "11_11") (pintype "passive"))
      (node (ref "U11") (pin "13") (pinfunction "13_13") (pintype "passive"))
      (node (ref "U11") (pin "15") (pinfunction "15_15") (pintype "passive"))
      (node (ref "U11") (pin "9") (pinfunction "9_9") (pintype "passive"))
      (node (ref "U2") (pin "10") (pinfunction "GND_10") (pintype "power_in"))
      (node (ref "U3") (pin "5") (pinfunction "GND_5") (pintype "passive"))
      (node (ref "U4") (pin "11") (pinfunction "11_11") (pintype "passive"))
      (node (ref "U4") (pin "13") (pinfunction "13_13") (pintype "passive"))
      (node (ref "U4") (pin "15") (pinfunction "15_15") (pintype "passive"))
      (node (ref "U4") (pin "9") (pinfunction "9_9") (pintype "passive"))
      (node (ref "U5") (pin "5") (pinfunction "GND_5") (pintype "passive"))
      (node (ref "U6") (pin "11") (pinfunction "11_11") (pintype "passive"))
      (node (ref "U6") (pin "13") (pinfunction "13_13") (pintype "passive"))
      (node (ref "U6") (pin "15") (pinfunction "15_15") (pintype "passive"))
      (node (ref "U6") (pin "9") (pinfunction "9_9") (pintype "passive"))
      (node (ref "U7") (pin "10") (pinfunction "GND_10") (pintype "power_in"))
      (node (ref "U8") (pin "5") (pinfunction "GND_5") (pintype "passive"))
      (node (ref "U9") (pin "11") (pinfunction "11_11") (pintype "passive"))
      (node (ref "U9") (pin "13") (pinfunction "13_13") (pintype "passive"))
      (node (ref "U9") (pin "15") (pinfunction "15_15") (pintype "passive"))
      (node (ref "U9") (pin "9") (pinfunction "9_9") (pintype "passive"))
    )
    (net (code "77") (name "Net-(R2-Pad1)") (class "Default")
      (node (ref "R2") (pin "1") (pinfunction "1_1") (pintype "passive"))
      (node (ref "U1") (pin "2") (pinfunction "2_2") (pintype "passive"))
    )
    (net (code "78") (name "Net-(R6-Pad1)") (class "Default")
      (node (ref "R6") (pin "1") (pinfunction "1_1") (pintype "passive"))
      (node (ref "U1") (pin "4") (pinfunction "4_4") (pintype "passive"))
    )
    (net (code "79") (name "Net-(R12-Pad1)") (class "Default")
      (node (ref "R12") (pin "1") (pinfunction "1_1") (pintype "passive"))
      (node (ref "U1") (pin "6") (pinfunction "6_6") (pintype "passive"))
    )
    (net (code "80") (name "Net-(R18-Pad1)") (class "Default")
      (node (ref "R18") (pin "1") (pinfunction "1_1") (pintype "passive"))
      (node (ref "U1") (pin "8") (pinfunction "8_8") (pintype "passive"))
    )
    (net (code "81") (name "Net-(R29-Pad1)") (class "Default")
      (node (ref "R29") (pin "1") (pinfunction "1_1") (pintype "passive"))
      (node (ref "U4") (pin "2") (pinfunction "2_2") (pintype "passive"))
    )
    (net (code "82") (name "Net-(R31-Pad1)") (class "Default")
      (node (ref "R31") (pin "1") (pinfunction "1_1") (pintype "passive"))
      (node (ref "U4") (pin "4") (pinfunction "4_4") (pintype "passive"))
    )
    (net (code "83") (name "Net-(R33-Pad1)") (class "Default")
      (node (ref "R33") (pin "1") (pinfunction "1_1") (pintype "passive"))
      (node (ref "U4") (pin "6") (pinfunction "6_6") (pintype "passive"))
    )
    (net (code "84") (name "Net-(R36-Pad1)") (class "Default")
      (node (ref "R36") (pin "1") (pinfunction "1_1") (pintype "passive"))
      (node (ref "U4") (pin "8") (pinfunction "8_8") (pintype "passive"))
    )
    (net (code "85") (name "Net-(R44-Pad1)") (class "Default")
      (node (ref "R44") (pin "1") (pinfunction "1_1") (pintype "passive"))
      (node (ref "U6") (pin "2") (pinfunction "2_2") (pintype "passive"))
    )
    (net (code "86") (name "Net-(R49-Pad1)") (class "Default")
      (node (ref "R49") (pin "1") (pinfunction "1_1") (pintype "passive"))
      (node (ref "U6") (pin "4") (pinfunction "4_4") (pintype "passive"))
    )
    (net (code "87") (name "Net-(R56-Pad1)") (class "Default")
      (node (ref "R56") (pin "1") (pinfunction "1_1") (pintype "passive"))
      (node (ref "U6") (pin "6") (pinfunction "6_6") (pintype "passive"))
    )
    (net (code "88") (name "Net-(R60-Pad1)") (class "Default")
      (node (ref "R60") (pin "1") (pinfunction "1_1") (pintype "passive"))
      (node (ref "U6") (pin "8") (pinfunction "8_8") (pintype "passive"))
    )
    (net (code "89") (name "Net-(R67-Pad1)") (class "Default")
      (node (ref "R67") (pin "1") (pinfunction "1_1") (pintype "passive"))
      (node (ref "U9") (pin "2") (pinfunction "2_2") (pintype "passive"))
    )
    (net (code "90") (name "Net-(R69-Pad1)") (class "Default")
      (node (ref "R69") (pin "1") (pinfunction "1_1") (pintype "passive"))
      (node (ref "U9") (pin "4") (pinfunction "4_4") (pintype "passive"))
    )
    (net (code "91") (name "Net-(R71-Pad1)") (class "Default")
      (node (ref "R71") (pin "1") (pinfunction "1_1") (pintype "passive"))
      (node (ref "U9") (pin "6") (pinfunction "6_6") (pintype "passive"))
    )
    (net (code "92") (name "Net-(R74-Pad1)") (class "Default")
      (node (ref "R74") (pin "1") (pinfunction "1_1") (pintype "passive"))
      (node (ref "U9") (pin "8") (pinfunction "8_8") (pintype "passive"))
    )
    (net (code "93") (name "Net-(R77-Pad1)") (class "Default")
      (node (ref "R77") (pin "1") (pinfunction "1_1") (pintype "passive"))
      (node (ref "U11") (pin "2") (pinfunction "2_2") (pintype "passive"))
    )
    (net (code "94") (name "Net-(R79-Pad1)") (class "Default")
      (node (ref "R79") (pin "1") (pinfunction "1_1") (pintype "passive"))
      (node (ref "U11") (pin "4") (pinfunction "4_4") (pintype "passive"))
    )
    (net (code "95") (name "Net-(R81-Pad1)") (class "Default")
      (node (ref "R81") (pin "1") (pinfunction "1_1") (pintype "passive"))
      (node (ref "U11") (pin "6") (pinfunction "6_6") (pintype "passive"))
    )
    (net (code "96") (name "Net-(R83-Pad1)") (class "Default")
      (node (ref "R83") (pin "1") (pinfunction "1_1") (pintype "passive"))
      (node (ref "U11") (pin "8") (pinfunction "8_8") (pintype "passive"))
    )
    (net (code "97") (name "Net-(U2-A0)") (class "Default")
      (node (ref "R16") (pin "2") (pinfunction "2_2") (pintype "passive"))
      (node (ref "U2") (pin "2") (pinfunction "A0_2") (pintype "bidirectional"))
    )
    (net (code "98") (name "Net-(U2-A1)") (class "Default")
      (node (ref "R19") (pin "2") (pinfunction "2_2") (pintype "passive"))
      (node (ref "U2") (pin "3") (pinfunction "A1_3") (pintype "bidirectional"))
    )
    (net (code "99") (name "Net-(U2-A2)") (class "Default")
      (node (ref "R22") (pin "2") (pinfunction "2_2") (pintype "passive"))
      (node (ref "U2") (pin "4") (pinfunction "A2_4") (pintype "bidirectional"))
    )
    (net (code "100") (name "Net-(U2-A3)") (class "Default")
      (node (ref "R23") (pin "2") (pinfunction "2_2") (pintype "passive"))
      (node (ref "U2") (pin "5") (pinfunction "A3_5") (pintype "bidirectional"))
    )
    (net (code "101") (name "Net-(U2-A4)") (class "Default")
      (node (ref "R25") (pin "2") (pinfunction "2_2") (pintype "passive"))
      (node (ref "U2") (pin "6") (pinfunction "A4_6") (pintype "bidirectional"))
    )
    (net (code "102") (name "Net-(U2-A5)") (class "Default")
      (node (ref "R26") (pin "2") (pinfunction "2_2") (pintype "passive"))
      (node (ref "U2") (pin "7") (pinfunction "A5_7") (pintype "bidirectional"))
    )
    (net (code "103") (name "Net-(U2-A6)") (class "Default")
      (node (ref "R27") (pin "2") (pinfunction "2_2") (pintype "passive"))
      (node (ref "U2") (pin "8") (pinfunction "A6_8") (pintype "bidirectional"))
    )
    (net (code "104") (name "Net-(U2-A7)") (class "Default")
      (node (ref "R28") (pin "2") (pinfunction "2_2") (pintype "passive"))
      (node (ref "U2") (pin "9") (pinfunction "A7_9") (pintype "bidirectional"))
    )
    (net (code "105") (name "Net-(U2-DIR)") (class "Default")
      (node (ref "R10") (pin "2") (pinfunction "2_2") (pintype "passive"))
      (node (ref "U2") (pin "1") (pinfunction "DIR_1") (pintype "input"))
    )
    (net (code "106") (name "Net-(U2-~{OE})") (class "Default")
      (node (ref "R7") (pin "2") (pinfunction "2_2") (pintype "passive"))
      (node (ref "U2") (pin "19") (pinfunction "~{OE}_19") (pintype "input"))
    )
    (net (code "107") (name "Net-(U3-IN-)") (class "Default")
      (node (ref "R24") (pin "2") (pinfunction "2_2") (pintype "passive"))
      (node (ref "U3") (pin "3") (pinfunction "IN-_3") (pintype "passive"))
    )
    (net (code "108") (name "Net-(U5-IN-)") (class "Default")
      (node (ref "R38") (pin "2") (pinfunction "2_2") (pintype "passive"))
      (node (ref "U5") (pin "3") (pinfunction "IN-_3") (pintype "passive"))
    )
    (net (code "109") (name "Net-(U7-A0)") (class "Default")
      (node (ref "R51") (pin "2") (pinfunction "2_2") (pintype "passive"))
      (node (ref "U7") (pin "2") (pinfunction "A0_2") (pintype "bidirectional"))
    )
    (net (code "110") (name "Net-(U7-A1)") (class "Default")
      (node (ref "R54") (pin "2") (pinfunction "2_2") (pintype "passive"))
      (node (ref "U7") (pin "3") (pinfunction "A1_3") (pintype "bidirectional"))
    )
    (net (code "111") (name "Net-(U7-A2)") (class "Default")
      (node (ref "R58") (pin "2") (pinfunction "2_2") (pintype "passive"))
      (node (ref "U7") (pin "4") (pinfunction "A2_4") (pintype "bidirectional"))
    )
    (net (code "112") (name "Net-(U7-A3)") (class "Default")
      (node (ref "R59") (pin "2") (pinfunction "2_2") (pintype "passive"))
      (node (ref "U7") (pin "5") (pinfunction "A3_5") (pintype "bidirectional"))
    )
    (net (code "113") (name "Net-(U7-A4)") (class "Default")
      (node (ref "R62") (pin "2") (pinfunction "2_2") (pintype "passive"))
      (node (ref "U7") (pin "6") (pinfunction "A4_6") (pintype "bidirectional"))
    )
    (net (code "114") (name "Net-(U7-A5)") (class "Default")
      (node (ref "R64") (pin "2") (pinfunction "2_2") (pintype "passive"))
      (node (ref "U7") (pin "7") (pinfunction "A5_7") (pintype "bidirectional"))
    )
    (net (code "115") (name "Net-(U7-A6)") (class "Default")
      (node (ref "R65") (pin "2") (pinfunction "2_2") (pintype "passive"))
      (node (ref "U7") (pin "8") (pinfunction "A6_8") (pintype "bidirectional"))
    )
    (net (code "116") (name "Net-(U7-A7)") (class "Default")
      (node (ref "R66") (pin "2") (pinfunction "2_2") (pintype "passive"))
      (node (ref "U7") (pin "9") (pinfunction "A7_9") (pintype "bidirectional"))
    )
    (net (code "117") (name "Net-(U7-DIR)") (class "Default")
      (node (ref "R46") (pin "2") (pinfunction "2_2") (pintype "passive"))
      (node (ref "U7") (pin "1") (pinfunction "DIR_1") (pintype "input"))
    )
    (net (code "118") (name "Net-(U7-~{OE})") (class "Default")
      (node (ref "R42") (pin "2") (pinfunction "2_2") (pintype "passive"))
      (node (ref "U7") (pin "19") (pinfunction "~{OE}_19") (pintype "input"))
    )
    (net (code "119") (name "Net-(U8-IN-)") (class "Default")
      (node (ref "R63") (pin "2") (pinfunction "2_2") (pintype "passive"))
      (node (ref "U8") (pin "3") (pinfunction "IN-_3") (pintype "passive"))
    )
    (net (code "120") (name "Net-(U10-IN-)") (class "Default")
      (node (ref "R76") (pin "2") (pinfunction "2_2") (pintype "passive"))
      (node (ref "U10") (pin "3") (pinfunction "IN-_3") (pintype "passive"))
    )
    (net (code "121") (name "unconnected-(U3-NC-Pad1)") (class "Default")
      (node (ref "U3") (pin "1") (pinfunction "NC_1") (pintype "passive"))
    )
    (net (code "122") (name "unconnected-(U3-NC-Pad4)") (class "Default")
      (node (ref "U3") (pin "4") (pinfunction "NC_4") (pintype "passive"))
    )
    (net (code "123") (name "unconnected-(U5-NC-Pad1)") (class "Default")
      (node (ref "U5") (pin "1") (pinfunction "NC_1") (pintype "passive"))
    )
    (net (code "124") (name "unconnected-(U5-NC-Pad4)") (class "Default")
      (node (ref "U5") (pin "4") (pinfunction "NC_4") (pintype "passive"))
    )
    (net (code "125") (name "unconnected-(U8-NC-Pad1)") (class "Default")
      (node (ref "U8") (pin "1") (pinfunction "NC_1") (pintype "passive"))
    )
    (net (code "126") (name "unconnected-(U8-NC-Pad4)") (class "Default")
      (node (ref "U8") (pin "4") (pinfunction "NC_4") (pintype "passive"))
    )
    (net (code "127") (name "unconnected-(U10-NC-Pad1)") (class "Default")
      (node (ref "U10") (pin "1") (pinfunction "NC_1") (pintype "passive"))
    )
    (net (code "128") (name "unconnected-(U10-NC-Pad4)") (class "Default")
      (node (ref "U10") (pin "4") (pinfunction "NC_4") (pintype "passive"))
    )
  )
)
